# MCU.net
KiCad netlist of a schematic drawn in Altium Designer
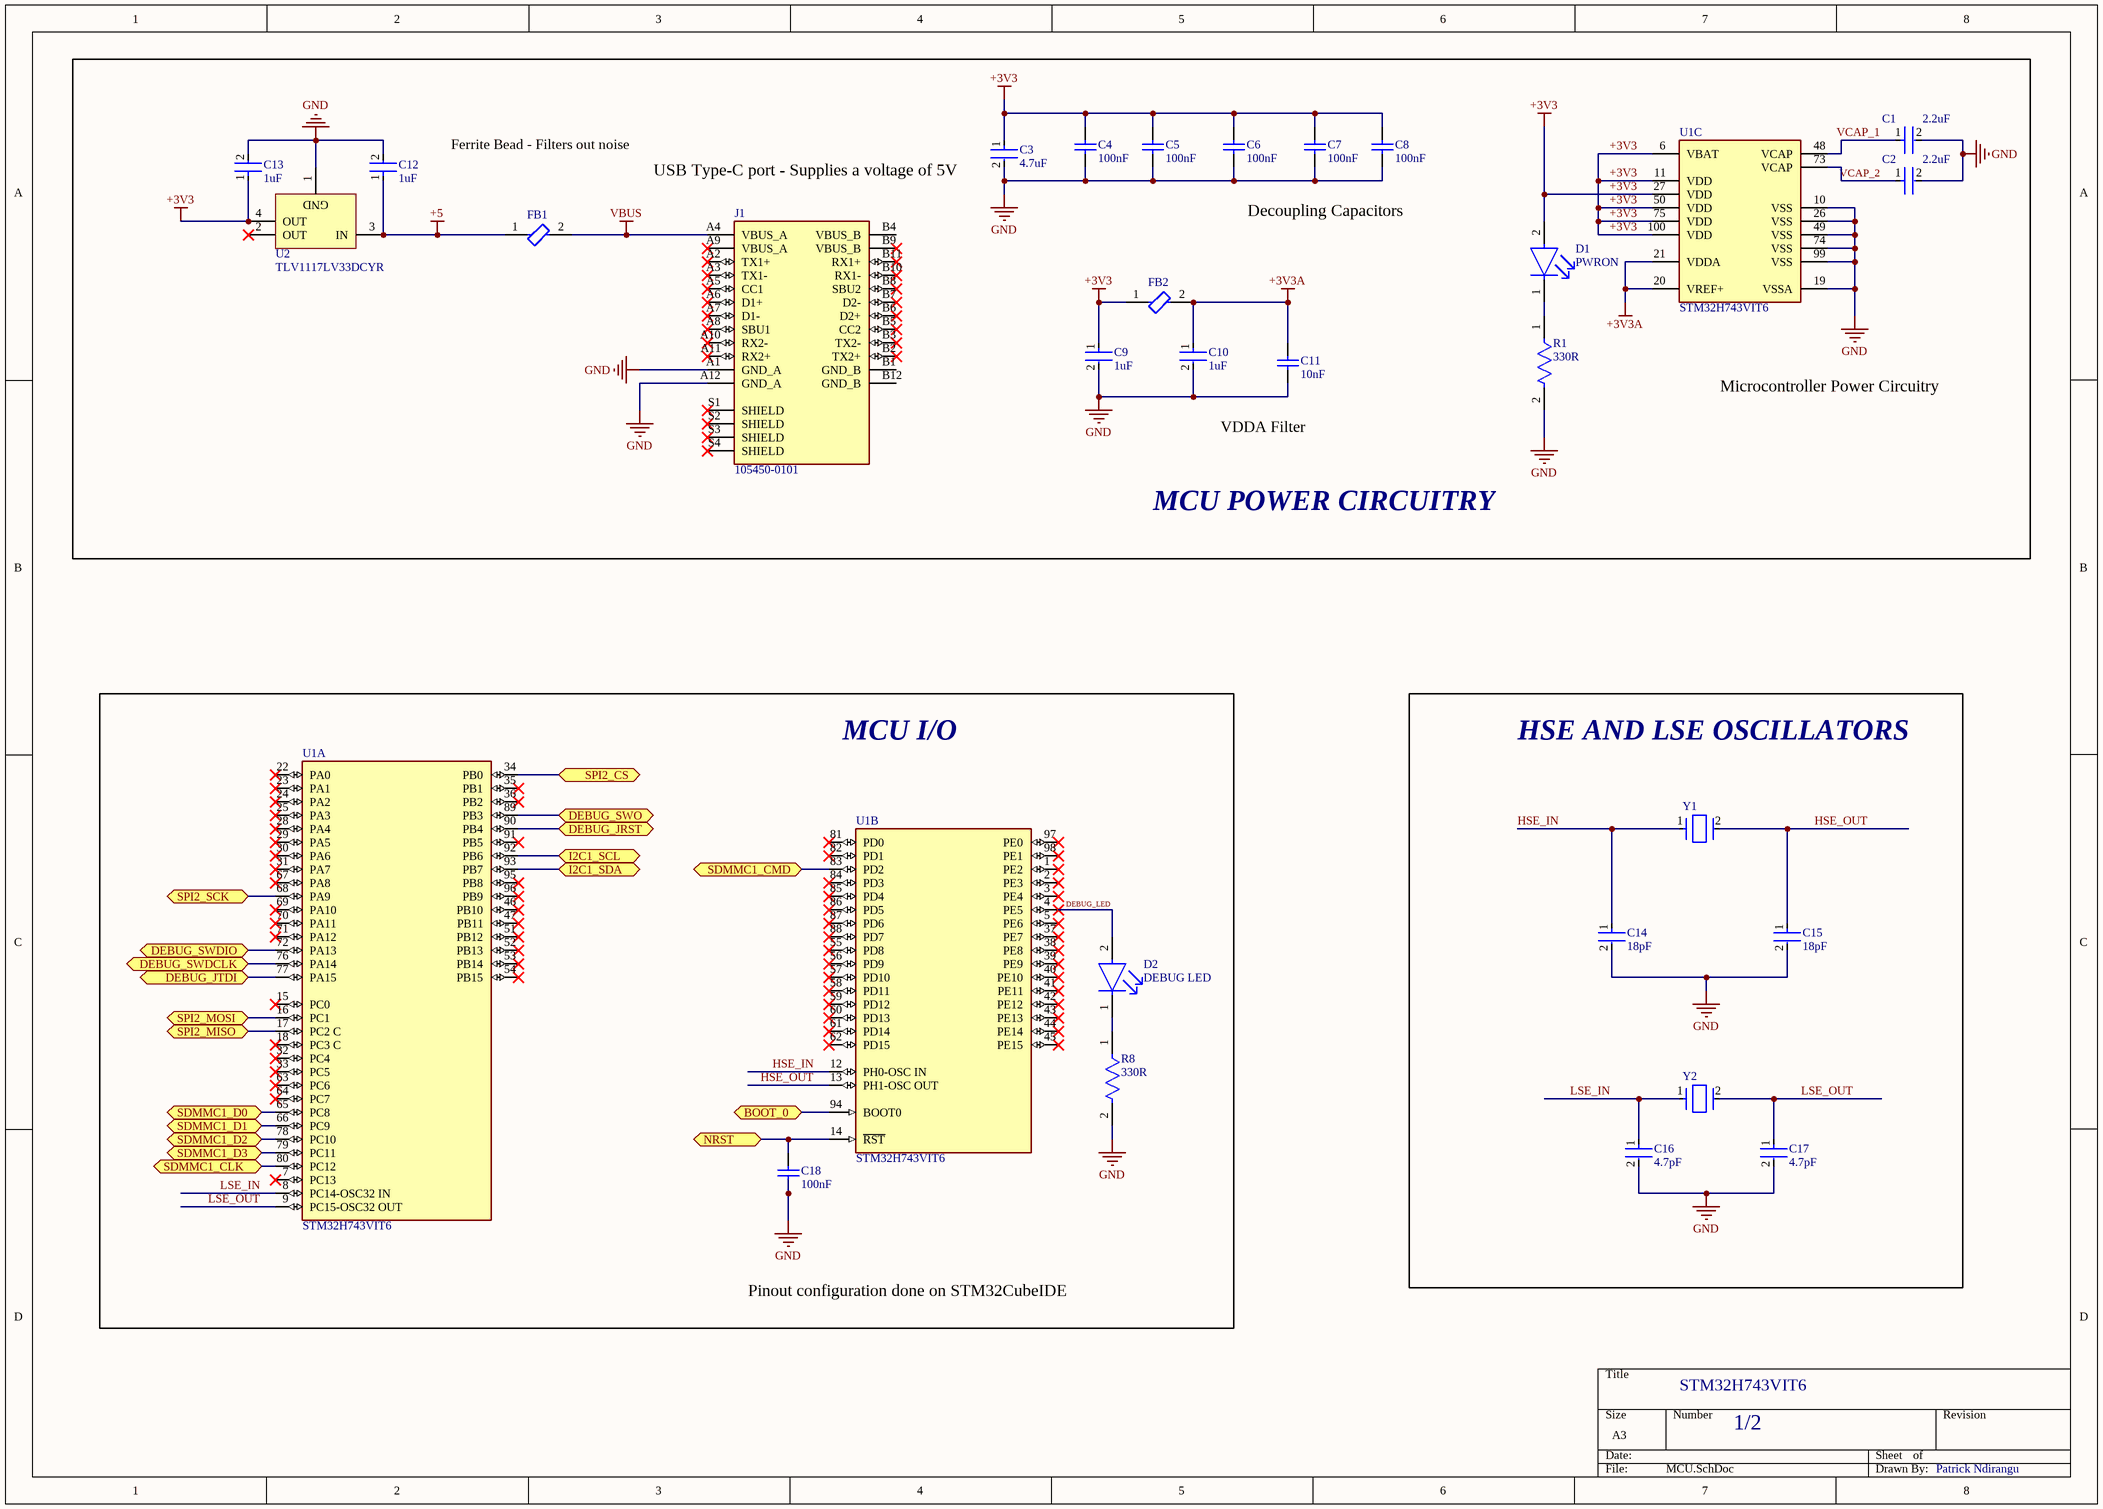
[diagram p0: MCU.SchDoc]

(export (version "E")
  (design (tool "Eeschema 10.0.6"))
  (components
    (comp (ref "C1")
      (value "2.2uF")
      (footprint "FP-0805-L_2_01_0_2-W_1_25-IPC_C")
      (description "General Purpose Ceramic Capacitor, 0805, 2.2uF, 10%, X5R, 15%, 25V")
      (fields (field (name "TOLERANCE") "10%"))
      (libsource (lib "Altium Content Vault") (part "b4654b650e69147ec39a6b967a45e02"))
    )
    (comp (ref "C2")
      (value "2.2uF")
      (footprint "FP-0805-L_2_01_0_2-W_1_25-IPC_C")
      (description "General Purpose Ceramic Capacitor, 0805, 2.2uF, 10%, X5R, 15%, 25V")
      (fields (field (name "TOLERANCE") "10%"))
      (libsource (lib "Altium Content Vault") (part "b4654b650e69147ec39a6b967a45e02"))
    )
    (comp (ref "C3")
      (value "4.7uF")
      (footprint "FP-CL21-IPC_A")
      (description "CL21 Series 0805 4.7uF 25V ±10% Tolerance X5R Multilayer Ceramic Chip Capacitor")
      (fields (field (name "TOLERANCE") "10%"))
      (libsource (lib "Altium Content Vault") (part "b4654b650e69147ec39a6b967a45e02"))
    )
    (comp (ref "C4")
      (value "100nF")
      (footprint "CAPC1050X55X23ML05T13")
      (description "Chip Capacitor, 100 nF, +/- 10%, 16 V, -55 to 125 degC, 0402 (1005 Metric), RoHS, Tape and Reel")
      (fields (field (name "MANUFACTURER") "Samsung Electro-Mechanics"))
      (libsource (lib "Altium Content Vault") (part "CAP-NP-2"))
    )
    (comp (ref "C5")
      (value "100nF")
      (footprint "CAPC1050X55X23ML05T13")
      (description "Chip Capacitor, 100 nF, +/- 10%, 16 V, -55 to 125 degC, 0402 (1005 Metric), RoHS, Tape and Reel")
      (fields (field (name "MANUFACTURER") "Samsung Electro-Mechanics"))
      (libsource (lib "Altium Content Vault") (part "CAP-NP-2"))
    )
    (comp (ref "C6")
      (value "100nF")
      (footprint "CAPC1050X55X23ML05T13")
      (description "Chip Capacitor, 100 nF, +/- 10%, 16 V, -55 to 125 degC, 0402 (1005 Metric), RoHS, Tape and Reel")
      (fields (field (name "MANUFACTURER") "Samsung Electro-Mechanics"))
      (libsource (lib "Altium Content Vault") (part "CAP-NP-2"))
    )
    (comp (ref "C7")
      (value "100nF")
      (footprint "CAPC1050X55X23ML05T13")
      (description "Chip Capacitor, 100 nF, +/- 10%, 16 V, -55 to 125 degC, 0402 (1005 Metric), RoHS, Tape and Reel")
      (fields (field (name "MANUFACTURER") "Samsung Electro-Mechanics"))
      (libsource (lib "Altium Content Vault") (part "CAP-NP-2"))
    )
    (comp (ref "C8")
      (value "100nF")
      (footprint "CAPC1050X55X23ML05T13")
      (description "Chip Capacitor, 100 nF, +/- 10%, 16 V, -55 to 125 degC, 0402 (1005 Metric), RoHS, Tape and Reel")
      (fields (field (name "MANUFACTURER") "Samsung Electro-Mechanics"))
      (libsource (lib "Altium Content Vault") (part "CAP-NP-2"))
    )
    (comp (ref "C9")
      (value "1uF")
      (footprint "FP-CL10-IPC_C")
      (description "Cap Ceramic 1uF 25V X5R ±10% Pad SMD 0603 +85°C T/R")
      (fields (field (name "VOLTAGE") "25V") (field (name "TOLERANCE") "10%"))
      (libsource (lib "Altium Content Vault") (part "b4654b650e69147ec39a6b967a45e02"))
    )
    (comp (ref "C10")
      (value "1uF")
      (footprint "FP-CL10-IPC_C")
      (description "Cap Ceramic 1uF 25V X5R ±10% Pad SMD 0603 +85°C T/R")
      (fields (field (name "VOLTAGE") "25V") (field (name "TOLERANCE") "10%"))
      (libsource (lib "Altium Content Vault") (part "b4654b650e69147ec39a6b967a45e02"))
    )
    (comp (ref "C11")
      (value "10nF")
      (footprint "CAPC1608X90X35ML10T15")
      (description "Chip Capacitor, 10 nF, +/- 10%, 50 V, -55 to 125 degC, 0603 (1608 Metric), RoHS, Tape and Reel")
      (fields (field (name "VOLTAGE") "50V") (field (name "TOLERANCE") "10%"))
      (libsource (lib "Altium Content Vault") (part "CAP-NP-2"))
    )
    (comp (ref "C12")
      (value "1uF")
      (footprint "FP-CL10-IPC_C")
      (description "Cap Ceramic 1uF 25V X5R ±10% Pad SMD 0603 +85°C T/R")
      (fields (field (name "VOLTAGE") "25V") (field (name "TOLERANCE") "10%"))
      (libsource (lib "Altium Content Vault") (part "b4654b650e69147ec39a6b967a45e02"))
    )
    (comp (ref "C13")
      (value "1uF")
      (footprint "FP-CL10-IPC_C")
      (description "Cap Ceramic 1uF 25V X5R ±10% Pad SMD 0603 +85°C T/R")
      (fields (field (name "VOLTAGE") "25V") (field (name "TOLERANCE") "10%"))
      (libsource (lib "Altium Content Vault") (part "b4654b650e69147ec39a6b967a45e02"))
    )
    (comp (ref "C14")
      (value "18pF")
      (footprint "FP-CL10-IPC_A")
      (description "Cap Ceramic 18pF 50V C0G ±5% Pad SMD 0603 +125°C T/R")
      (fields (field (name "TOLERANCE") "5%") (field (name "VOLTAGE") "50V"))
      (libsource (lib "Altium Content Vault") (part "b4654b650e69147ec39a6b967a45e02"))
    )
    (comp (ref "C15")
      (value "18pF")
      (footprint "FP-CL10-IPC_A")
      (description "Cap Ceramic 18pF 50V C0G ±5% Pad SMD 0603 +125°C T/R")
      (fields (field (name "TOLERANCE") "5%") (field (name "VOLTAGE") "50V"))
      (libsource (lib "Altium Content Vault") (part "b4654b650e69147ec39a6b967a45e02"))
    )
    (comp (ref "C16")
      (value "4.7pF")
      (footprint "FP-CL10-IPC_C")
      (description "Cap Ceramic 4.7pF 50V C0G ±0.25pF Pad SMD 0603 +125°C T/R")
      (fields (field (name "VOLTAGE") "50V"))
      (libsource (lib "Altium Content Vault") (part "b4654b650e69147ec39a6b967a45e02"))
    )
    (comp (ref "C17")
      (value "4.7pF")
      (footprint "FP-CL10-IPC_C")
      (description "Cap Ceramic 4.7pF 50V C0G ±0.25pF Pad SMD 0603 +125°C T/R")
      (fields (field (name "VOLTAGE") "50V"))
      (libsource (lib "Altium Content Vault") (part "b4654b650e69147ec39a6b967a45e02"))
    )
    (comp (ref "C18")
      (value "100nF")
      (footprint "CAPC1050X55X23ML05T13")
      (description "Chip Capacitor, 100 nF, +/- 10%, 16 V, -55 to 125 degC, 0402 (1005 Metric), RoHS, Tape and Reel")
      (fields (field (name "MANUFACTURER") "Samsung Electro-Mechanics"))
      (libsource (lib "Altium Content Vault") (part "CAP-NP-2"))
    )
    (comp (ref "D1")
      (value "PWRON")
      (footprint "FP-6_541-5092_01-4-MFG")
      (description "LED RED 0603 SMD")
      (fields
        (field (name "MANUFACTURER") "Vishay")
        (field (name "MANUFACTURER PART NUMBER") "VLMS1300-GS08")
      )
      (libsource (lib "Altium Content Vault") (part "8706943c75ba83719d021d2fdc84c58"))
    )
    (comp (ref "D2")
      (value "DEBUG LED")
      (footprint "FP-6_541-5094_01-4-MFG")
      (description "LED BLUE 0603 SMD")
      (fields
        (field (name "MANUFACTURER PART NUMBER") "VLMB1300-GS08")
        (field (name "MANUFACTURER") "Vishay Semiconductor Opto Division")
      )
      (libsource (lib "Altium Content Vault") (part "8706943c75ba83719d021d2fdc84c58"))
    )
    (comp (ref "FB1")
      (value "MMZ1005D121CTD25")
      (footprint "FP-MMZ1005-IPC_C")
      (description "Signal Line Ferrite Bead 120Ω @ 100MHz 350mA DCR 600mΩ AEC-Q200 SMD 0402")
      (libsource (lib "Altium Content Vault") (part "5f30dd21d616792df468990f7003faa"))
    )
    (comp (ref "FB2")
      (value "MMZ1005D121CTD25")
      (footprint "FP-MMZ1005-IPC_C")
      (description "Signal Line Ferrite Bead 120Ω @ 100MHz 350mA DCR 600mΩ AEC-Q200 SMD 0402")
      (libsource (lib "Altium Content Vault") (part "5f30dd21d616792df468990f7003faa"))
    )
    (comp (ref "J1")
      (value "105450-0101")
      (footprint "MOLEX_105450-0101")
      (fields
        (field (name "MF") "Molex")
        (field (name "DIGI-KEY_PART_NUMBER") "WM12856TR-ND")
        (field (name "MP") "1054500101")
      )
      (libsource (lib "105450-0101") (part "105450-0101"))
    )
    (comp (ref "R1")
      (value "330R")
      (footprint "FP-KTR03-MFG")
      (description "Res Thick Film 0603 330Ω 1% 0.1W ±100ppm/°C Automotive Paper T/R")
      (fields (field (name "TOLERANCE") "1%"))
      (libsource (lib "Altium Content Vault") (part "1029c3af85768c4190bb7ad29bc67b5"))
    )
    (comp (ref "R8")
      (value "330R")
      (footprint "FP-KTR03-MFG")
      (description "Res Thick Film 0603 330Ω 1% 0.1W ±100ppm/°C Automotive Paper T/R")
      (fields (field (name "TOLERANCE") "1%"))
      (libsource (lib "Altium Content Vault") (part "1029c3af85768c4190bb7ad29bc67b5"))
    )
    (comp (ref "U1")
      (value "STM32H743VIT6")
      (footprint "FP-LQFP100-1L-MFG")
      (description "IC MCU 32BIT 2MB FLASH 100LQFP")
      (fields
        (field (name "OCTOPART") "https://octopart.com/stm32h743vit6-stmicroelectronics-76372527")
        (field (name "MANUFACTURER") "STMicroelectronics")
      )
      (libsource (lib "Altium Content Vault") (part "01082ce2885d1d16a22823c45526fe6"))
    )
    (comp (ref "U2")
      (value "TLV1117LV33DCYR")
      (footprint "DCY0004A_N")
      (fields (field (name "MANUFACTURER") "Texas Instruments"))
      (libsource (lib "Altium Content Vault") (part "TI-TLV1117LV33DCY4"))
    )
    (comp (ref "Y1")
      (value "ABM2-25.000MHZ-D4Y-T")
      (footprint "FP-ABM2-MFG")
      (description "Crystal 25MHz ±30ppm 18pF SMD-2 8mm x 4.5mm")
      (fields (field (name "TOLERANCE") "30ppm"))
      (libsource (lib "Altium Content Vault") (part "c23a69dc6c9e2f18f2079038eb95dd1"))
    )
    (comp (ref "Y2")
      (value "ABS06-107-32.768KHZ-T")
      (footprint "FP-ABS06-MFG")
      (description "Crystal 32.768kHz ±20ppm (Tol) 4pF FUND 60kΩ 2-Pin Mini-CSMD T/R")
      (fields (field (name "TOLERANCE") "20ppm"))
      (libsource (lib "Altium Content Vault") (part "c23a69dc6c9e2f18f2079038eb95dd1"))
    )
  )
  (nets
    (net (code "1") (name "+3V3") (class "Default")
      (node (ref "C13") (pin "1") (pinfunction "1_1") (pintype "passive"))
      (node (ref "C3") (pin "1") (pinfunction "1_1") (pintype "passive"))
      (node (ref "C4") (pin "2") (pinfunction "2_2") (pintype "passive"))
      (node (ref "C5") (pin "2") (pinfunction "2_2") (pintype "passive"))
      (node (ref "C6") (pin "2") (pinfunction "2_2") (pintype "passive"))
      (node (ref "C7") (pin "2") (pinfunction "2_2") (pintype "passive"))
      (node (ref "C8") (pin "2") (pinfunction "2_2") (pintype "passive"))
      (node (ref "C9") (pin "1") (pinfunction "1_1") (pintype "passive"))
      (node (ref "D1") (pin "2") (pinfunction "A_2") (pintype "passive"))
      (node (ref "FB2") (pin "1") (pinfunction "1_1") (pintype "passive"))
      (node (ref "U1") (pin "100") (pinfunction "VDD_100") (pintype "power_in"))
      (node (ref "U1") (pin "11") (pinfunction "VDD_11") (pintype "power_in"))
      (node (ref "U1") (pin "27") (pinfunction "VDD_27") (pintype "power_in"))
      (node (ref "U1") (pin "50") (pinfunction "VDD_50") (pintype "power_in"))
      (node (ref "U1") (pin "6") (pinfunction "VBAT_6") (pintype "power_in"))
      (node (ref "U1") (pin "75") (pinfunction "VDD_75") (pintype "power_in"))
      (node (ref "U2") (pin "4") (pinfunction "OUT_4") (pintype "power_in"))
    )
    (net (code "2") (name "+3V3A") (class "Default")
      (node (ref "C10") (pin "1") (pinfunction "1_1") (pintype "passive"))
      (node (ref "C11") (pin "2") (pinfunction "2_2") (pintype "passive"))
      (node (ref "FB2") (pin "2") (pinfunction "2_2") (pintype "passive"))
      (node (ref "U1") (pin "20") (pinfunction "VREF+_20") (pintype "power_in"))
      (node (ref "U1") (pin "21") (pinfunction "VDDA_21") (pintype "power_in"))
    )
    (net (code "3") (name "+5") (class "Default")
      (node (ref "C12") (pin "1") (pinfunction "1_1") (pintype "passive"))
      (node (ref "FB1") (pin "1") (pinfunction "1_1") (pintype "passive"))
      (node (ref "U2") (pin "3") (pinfunction "IN_3") (pintype "power_in"))
    )
    (net (code "4") (name "/BOOT_0") (class "Default")
      (node (ref "U1") (pin "94") (pinfunction "BOOT0_94") (pintype "input"))
    )
    (net (code "5") (name "/DEBUG_JRST") (class "Default")
      (node (ref "U1") (pin "90") (pinfunction "PB4_90") (pintype "bidirectional"))
    )
    (net (code "6") (name "/DEBUG_JTDI") (class "Default")
      (node (ref "U1") (pin "77") (pinfunction "PA15_77") (pintype "bidirectional"))
    )
    (net (code "7") (name "/DEBUG_LED") (class "Default")
      (node (ref "D2") (pin "2") (pinfunction "A_2") (pintype "passive"))
      (node (ref "U1") (pin "4") (pinfunction "PE5_4") (pintype "bidirectional"))
    )
    (net (code "8") (name "/DEBUG_SWDCLK") (class "Default")
      (node (ref "U1") (pin "76") (pinfunction "PA14_76") (pintype "bidirectional"))
    )
    (net (code "9") (name "/DEBUG_SWDIO") (class "Default")
      (node (ref "U1") (pin "72") (pinfunction "PA13_72") (pintype "bidirectional"))
    )
    (net (code "10") (name "/DEBUG_SWO") (class "Default")
      (node (ref "U1") (pin "89") (pinfunction "PB3_89") (pintype "bidirectional"))
    )
    (net (code "11") (name "/HSE_IN") (class "Default")
      (node (ref "C14") (pin "1") (pinfunction "1_1") (pintype "passive"))
      (node (ref "U1") (pin "12") (pinfunction "PH0-OSC_IN_12") (pintype "bidirectional"))
      (node (ref "Y1") (pin "1") (pinfunction "1_1") (pintype "passive"))
    )
    (net (code "12") (name "/HSE_OUT") (class "Default")
      (node (ref "C15") (pin "1") (pinfunction "1_1") (pintype "passive"))
      (node (ref "U1") (pin "13") (pinfunction "PH1-OSC_OUT_13") (pintype "bidirectional"))
      (node (ref "Y1") (pin "2") (pinfunction "2_2") (pintype "passive"))
    )
    (net (code "13") (name "/I2C1_SCL") (class "Default")
      (node (ref "U1") (pin "92") (pinfunction "PB6_92") (pintype "bidirectional"))
    )
    (net (code "14") (name "/I2C1_SDA") (class "Default")
      (node (ref "U1") (pin "93") (pinfunction "PB7_93") (pintype "bidirectional"))
    )
    (net (code "15") (name "/LSE_IN") (class "Default")
      (node (ref "C16") (pin "1") (pinfunction "1_1") (pintype "passive"))
      (node (ref "U1") (pin "8") (pinfunction "PC14-OSC32_IN_8") (pintype "bidirectional"))
      (node (ref "Y2") (pin "1") (pinfunction "1_1") (pintype "passive"))
    )
    (net (code "16") (name "/LSE_OUT") (class "Default")
      (node (ref "C17") (pin "1") (pinfunction "1_1") (pintype "passive"))
      (node (ref "U1") (pin "9") (pinfunction "PC15-OSC32_OUT_9") (pintype "bidirectional"))
      (node (ref "Y2") (pin "2") (pinfunction "2_2") (pintype "passive"))
    )
    (net (code "17") (name "/NRST") (class "Default")
      (node (ref "C18") (pin "2") (pinfunction "2_2") (pintype "passive"))
      (node (ref "U1") (pin "14") (pinfunction "~{RST}_14") (pintype "input"))
    )
    (net (code "18") (name "/SDMMC1_CLK") (class "Default")
      (node (ref "U1") (pin "80") (pinfunction "PC12_80") (pintype "bidirectional"))
    )
    (net (code "19") (name "/SDMMC1_CMD") (class "Default")
      (node (ref "U1") (pin "83") (pinfunction "PD2_83") (pintype "bidirectional"))
    )
    (net (code "20") (name "/SDMMC1_D0") (class "Default")
      (node (ref "U1") (pin "65") (pinfunction "PC8_65") (pintype "bidirectional"))
    )
    (net (code "21") (name "/SDMMC1_D1") (class "Default")
      (node (ref "U1") (pin "66") (pinfunction "PC9_66") (pintype "bidirectional"))
    )
    (net (code "22") (name "/SDMMC1_D2") (class "Default")
      (node (ref "U1") (pin "78") (pinfunction "PC10_78") (pintype "bidirectional"))
    )
    (net (code "23") (name "/SDMMC1_D3") (class "Default")
      (node (ref "U1") (pin "79") (pinfunction "PC11_79") (pintype "bidirectional"))
    )
    (net (code "24") (name "/SPI2_CS") (class "Default")
      (node (ref "U1") (pin "34") (pinfunction "PB0_34") (pintype "bidirectional"))
    )
    (net (code "25") (name "/SPI2_MISO") (class "Default")
      (node (ref "U1") (pin "17") (pinfunction "PC2_C_17") (pintype "bidirectional"))
    )
    (net (code "26") (name "/SPI2_MOSI") (class "Default")
      (node (ref "U1") (pin "16") (pinfunction "PC1_16") (pintype "bidirectional"))
    )
    (net (code "27") (name "/SPI2_SCK") (class "Default")
      (node (ref "U1") (pin "68") (pinfunction "PA9_68") (pintype "bidirectional"))
    )
    (net (code "28") (name "/VCAP_1") (class "Default")
      (node (ref "C1") (pin "1") (pinfunction "1_1") (pintype "passive"))
      (node (ref "U1") (pin "48") (pinfunction "VCAP_48") (pintype "passive"))
    )
    (net (code "29") (name "/VCAP_2") (class "Default")
      (node (ref "C2") (pin "1") (pinfunction "1_1") (pintype "passive"))
      (node (ref "U1") (pin "73") (pinfunction "VCAP_73") (pintype "passive"))
    )
    (net (code "30") (name "GND") (class "Default")
      (node (ref "C1") (pin "2") (pinfunction "2_2") (pintype "passive"))
      (node (ref "C10") (pin "2") (pinfunction "2_2") (pintype "passive"))
      (node (ref "C11") (pin "1") (pinfunction "1_1") (pintype "passive"))
      (node (ref "C12") (pin "2") (pinfunction "2_2") (pintype "passive"))
      (node (ref "C13") (pin "2") (pinfunction "2_2") (pintype "passive"))
      (node (ref "C14") (pin "2") (pinfunction "2_2") (pintype "passive"))
      (node (ref "C15") (pin "2") (pinfunction "2_2") (pintype "passive"))
      (node (ref "C16") (pin "2") (pinfunction "2_2") (pintype "passive"))
      (node (ref "C17") (pin "2") (pinfunction "2_2") (pintype "passive"))
      (node (ref "C18") (pin "1") (pinfunction "1_1") (pintype "passive"))
      (node (ref "C2") (pin "2") (pinfunction "2_2") (pintype "passive"))
      (node (ref "C3") (pin "2") (pinfunction "2_2") (pintype "passive"))
      (node (ref "C4") (pin "1") (pinfunction "1_1") (pintype "passive"))
      (node (ref "C5") (pin "1") (pinfunction "1_1") (pintype "passive"))
      (node (ref "C6") (pin "1") (pinfunction "1_1") (pintype "passive"))
      (node (ref "C7") (pin "1") (pinfunction "1_1") (pintype "passive"))
      (node (ref "C8") (pin "1") (pinfunction "1_1") (pintype "passive"))
      (node (ref "C9") (pin "2") (pinfunction "2_2") (pintype "passive"))
      (node (ref "J1") (pin "A1") (pinfunction "GND_A_A1") (pintype "power_in"))
      (node (ref "J1") (pin "A12") (pinfunction "GND_A_A12") (pintype "power_in"))
      (node (ref "R1") (pin "2") (pinfunction "2_2") (pintype "passive"))
      (node (ref "R8") (pin "2") (pinfunction "2_2") (pintype "passive"))
      (node (ref "U1") (pin "10") (pinfunction "VSS_10") (pintype "power_in"))
      (node (ref "U1") (pin "19") (pinfunction "VSSA_19") (pintype "power_in"))
      (node (ref "U1") (pin "26") (pinfunction "VSS_26") (pintype "power_in"))
      (node (ref "U1") (pin "49") (pinfunction "VSS_49") (pintype "power_in"))
      (node (ref "U1") (pin "74") (pinfunction "VSS_74") (pintype "power_in"))
      (node (ref "U1") (pin "99") (pinfunction "VSS_99") (pintype "power_in"))
      (node (ref "U2") (pin "1") (pinfunction "GND_1") (pintype "power_in"))
    )
    (net (code "31") (name "Net-(D1-C)") (class "Default")
      (node (ref "D1") (pin "1") (pinfunction "C_1") (pintype "passive"))
      (node (ref "R1") (pin "1") (pinfunction "1_1") (pintype "passive"))
    )
    (net (code "32") (name "Net-(D2-C)") (class "Default")
      (node (ref "D2") (pin "1") (pinfunction "C_1") (pintype "passive"))
      (node (ref "R8") (pin "1") (pinfunction "1_1") (pintype "passive"))
    )
    (net (code "33") (name "VBUS") (class "Default")
      (node (ref "FB1") (pin "2") (pinfunction "2_2") (pintype "passive"))
      (node (ref "J1") (pin "A4") (pinfunction "VBUS_A_A4") (pintype "power_in"))
    )
    (net (code "34") (name "unconnected-(J1-CC1-PadA5)") (class "Default")
      (node (ref "J1") (pin "A5") (pinfunction "CC1_A5") (pintype "bidirectional+no_connect"))
    )
    (net (code "35") (name "unconnected-(J1-CC2-PadB5)") (class "Default")
      (node (ref "J1") (pin "B5") (pinfunction "CC2_B5") (pintype "bidirectional+no_connect"))
    )
    (net (code "36") (name "unconnected-(J1-D1+-PadA6)") (class "Default")
      (node (ref "J1") (pin "A6") (pinfunction "D1+_A6") (pintype "bidirectional+no_connect"))
    )
    (net (code "37") (name "unconnected-(J1-D1--PadA7)") (class "Default")
      (node (ref "J1") (pin "A7") (pinfunction "D1-_A7") (pintype "bidirectional+no_connect"))
    )
    (net (code "38") (name "unconnected-(J1-D2+-PadB6)") (class "Default")
      (node (ref "J1") (pin "B6") (pinfunction "D2+_B6") (pintype "bidirectional+no_connect"))
    )
    (net (code "39") (name "unconnected-(J1-D2--PadB7)") (class "Default")
      (node (ref "J1") (pin "B7") (pinfunction "D2-_B7") (pintype "bidirectional+no_connect"))
    )
    (net (code "40") (name "unconnected-(J1-GND_B-PadB1)") (class "Default")
      (node (ref "J1") (pin "B1") (pinfunction "GND_B_B1") (pintype "power_in"))
    )
    (net (code "41") (name "unconnected-(J1-GND_B-PadB12)") (class "Default")
      (node (ref "J1") (pin "B12") (pinfunction "GND_B_B12") (pintype "power_in"))
    )
    (net (code "42") (name "unconnected-(J1-RX1+-PadB11)") (class "Default")
      (node (ref "J1") (pin "B11") (pinfunction "RX1+_B11") (pintype "bidirectional+no_connect"))
    )
    (net (code "43") (name "unconnected-(J1-RX1--PadB10)") (class "Default")
      (node (ref "J1") (pin "B10") (pinfunction "RX1-_B10") (pintype "bidirectional+no_connect"))
    )
    (net (code "44") (name "unconnected-(J1-RX2+-PadA11)") (class "Default")
      (node (ref "J1") (pin "A11") (pinfunction "RX2+_A11") (pintype "bidirectional+no_connect"))
    )
    (net (code "45") (name "unconnected-(J1-RX2--PadA10)") (class "Default")
      (node (ref "J1") (pin "A10") (pinfunction "RX2-_A10") (pintype "bidirectional+no_connect"))
    )
    (net (code "46") (name "unconnected-(J1-SBU1-PadA8)") (class "Default")
      (node (ref "J1") (pin "A8") (pinfunction "SBU1_A8") (pintype "bidirectional+no_connect"))
    )
    (net (code "47") (name "unconnected-(J1-SBU2-PadB8)") (class "Default")
      (node (ref "J1") (pin "B8") (pinfunction "SBU2_B8") (pintype "bidirectional+no_connect"))
    )
    (net (code "48") (name "unconnected-(J1-SHIELD-PadS1)") (class "Default")
      (node (ref "J1") (pin "S1") (pinfunction "SHIELD_S1") (pintype "passive+no_connect"))
    )
    (net (code "49") (name "unconnected-(J1-SHIELD-PadS2)") (class "Default")
      (node (ref "J1") (pin "S2") (pinfunction "SHIELD_S2") (pintype "passive+no_connect"))
    )
    (net (code "50") (name "unconnected-(J1-SHIELD-PadS3)") (class "Default")
      (node (ref "J1") (pin "S3") (pinfunction "SHIELD_S3") (pintype "passive+no_connect"))
    )
    (net (code "51") (name "unconnected-(J1-SHIELD-PadS4)") (class "Default")
      (node (ref "J1") (pin "S4") (pinfunction "SHIELD_S4") (pintype "passive+no_connect"))
    )
    (net (code "52") (name "unconnected-(J1-TX1+-PadA2)") (class "Default")
      (node (ref "J1") (pin "A2") (pinfunction "TX1+_A2") (pintype "bidirectional+no_connect"))
    )
    (net (code "53") (name "unconnected-(J1-TX1--PadA3)") (class "Default")
      (node (ref "J1") (pin "A3") (pinfunction "TX1-_A3") (pintype "bidirectional+no_connect"))
    )
    (net (code "54") (name "unconnected-(J1-TX2+-PadB2)") (class "Default")
      (node (ref "J1") (pin "B2") (pinfunction "TX2+_B2") (pintype "bidirectional+no_connect"))
    )
    (net (code "55") (name "unconnected-(J1-TX2--PadB3)") (class "Default")
      (node (ref "J1") (pin "B3") (pinfunction "TX2-_B3") (pintype "bidirectional+no_connect"))
    )
    (net (code "56") (name "unconnected-(J1-VBUS_A-PadA9)") (class "Default")
      (node (ref "J1") (pin "A9") (pinfunction "VBUS_A_A9") (pintype "power_in+no_connect"))
    )
    (net (code "57") (name "unconnected-(J1-VBUS_B-PadB4)") (class "Default")
      (node (ref "J1") (pin "B4") (pinfunction "VBUS_B_B4") (pintype "power_in"))
    )
    (net (code "58") (name "unconnected-(J1-VBUS_B-PadB9)") (class "Default")
      (node (ref "J1") (pin "B9") (pinfunction "VBUS_B_B9") (pintype "power_in+no_connect"))
    )
    (net (code "59") (name "unconnected-(U1A-PA0-Pad22)") (class "Default")
      (node (ref "U1") (pin "22") (pinfunction "PA0_22") (pintype "bidirectional+no_connect"))
    )
    (net (code "60") (name "unconnected-(U1A-PA1-Pad23)") (class "Default")
      (node (ref "U1") (pin "23") (pinfunction "PA1_23") (pintype "bidirectional+no_connect"))
    )
    (net (code "61") (name "unconnected-(U1A-PA2-Pad24)") (class "Default")
      (node (ref "U1") (pin "24") (pinfunction "PA2_24") (pintype "bidirectional+no_connect"))
    )
    (net (code "62") (name "unconnected-(U1A-PA3-Pad25)") (class "Default")
      (node (ref "U1") (pin "25") (pinfunction "PA3_25") (pintype "bidirectional+no_connect"))
    )
    (net (code "63") (name "unconnected-(U1A-PA4-Pad28)") (class "Default")
      (node (ref "U1") (pin "28") (pinfunction "PA4_28") (pintype "bidirectional+no_connect"))
    )
    (net (code "64") (name "unconnected-(U1A-PA5-Pad29)") (class "Default")
      (node (ref "U1") (pin "29") (pinfunction "PA5_29") (pintype "bidirectional+no_connect"))
    )
    (net (code "65") (name "unconnected-(U1A-PA6-Pad30)") (class "Default")
      (node (ref "U1") (pin "30") (pinfunction "PA6_30") (pintype "bidirectional+no_connect"))
    )
    (net (code "66") (name "unconnected-(U1A-PA7-Pad31)") (class "Default")
      (node (ref "U1") (pin "31") (pinfunction "PA7_31") (pintype "bidirectional+no_connect"))
    )
    (net (code "67") (name "unconnected-(U1A-PA8-Pad67)") (class "Default")
      (node (ref "U1") (pin "67") (pinfunction "PA8_67") (pintype "bidirectional+no_connect"))
    )
    (net (code "68") (name "unconnected-(U1A-PA10-Pad69)") (class "Default")
      (node (ref "U1") (pin "69") (pinfunction "PA10_69") (pintype "bidirectional+no_connect"))
    )
    (net (code "69") (name "unconnected-(U1A-PA11-Pad70)") (class "Default")
      (node (ref "U1") (pin "70") (pinfunction "PA11_70") (pintype "bidirectional+no_connect"))
    )
    (net (code "70") (name "unconnected-(U1A-PA12-Pad71)") (class "Default")
      (node (ref "U1") (pin "71") (pinfunction "PA12_71") (pintype "bidirectional+no_connect"))
    )
    (net (code "71") (name "unconnected-(U1A-PB1-Pad35)") (class "Default")
      (node (ref "U1") (pin "35") (pinfunction "PB1_35") (pintype "bidirectional+no_connect"))
    )
    (net (code "72") (name "unconnected-(U1A-PB2-Pad36)") (class "Default")
      (node (ref "U1") (pin "36") (pinfunction "PB2_36") (pintype "bidirectional+no_connect"))
    )
    (net (code "73") (name "unconnected-(U1A-PB5-Pad91)") (class "Default")
      (node (ref "U1") (pin "91") (pinfunction "PB5_91") (pintype "bidirectional+no_connect"))
    )
    (net (code "74") (name "unconnected-(U1A-PB8-Pad95)") (class "Default")
      (node (ref "U1") (pin "95") (pinfunction "PB8_95") (pintype "bidirectional+no_connect"))
    )
    (net (code "75") (name "unconnected-(U1A-PB9-Pad96)") (class "Default")
      (node (ref "U1") (pin "96") (pinfunction "PB9_96") (pintype "bidirectional+no_connect"))
    )
    (net (code "76") (name "unconnected-(U1A-PB10-Pad46)") (class "Default")
      (node (ref "U1") (pin "46") (pinfunction "PB10_46") (pintype "bidirectional+no_connect"))
    )
    (net (code "77") (name "unconnected-(U1A-PB11-Pad47)") (class "Default")
      (node (ref "U1") (pin "47") (pinfunction "PB11_47") (pintype "bidirectional+no_connect"))
    )
    (net (code "78") (name "unconnected-(U1A-PB12-Pad51)") (class "Default")
      (node (ref "U1") (pin "51") (pinfunction "PB12_51") (pintype "bidirectional+no_connect"))
    )
    (net (code "79") (name "unconnected-(U1A-PB13-Pad52)") (class "Default")
      (node (ref "U1") (pin "52") (pinfunction "PB13_52") (pintype "bidirectional+no_connect"))
    )
    (net (code "80") (name "unconnected-(U1A-PB14-Pad53)") (class "Default")
      (node (ref "U1") (pin "53") (pinfunction "PB14_53") (pintype "bidirectional+no_connect"))
    )
    (net (code "81") (name "unconnected-(U1A-PB15-Pad54)") (class "Default")
      (node (ref "U1") (pin "54") (pinfunction "PB15_54") (pintype "bidirectional+no_connect"))
    )
    (net (code "82") (name "unconnected-(U1A-PC0-Pad15)") (class "Default")
      (node (ref "U1") (pin "15") (pinfunction "PC0_15") (pintype "bidirectional+no_connect"))
    )
    (net (code "83") (name "unconnected-(U1A-PC3_C-Pad18)") (class "Default")
      (node (ref "U1") (pin "18") (pinfunction "PC3_C_18") (pintype "bidirectional+no_connect"))
    )
    (net (code "84") (name "unconnected-(U1A-PC4-Pad32)") (class "Default")
      (node (ref "U1") (pin "32") (pinfunction "PC4_32") (pintype "bidirectional+no_connect"))
    )
    (net (code "85") (name "unconnected-(U1A-PC5-Pad33)") (class "Default")
      (node (ref "U1") (pin "33") (pinfunction "PC5_33") (pintype "bidirectional+no_connect"))
    )
    (net (code "86") (name "unconnected-(U1A-PC6-Pad63)") (class "Default")
      (node (ref "U1") (pin "63") (pinfunction "PC6_63") (pintype "bidirectional+no_connect"))
    )
    (net (code "87") (name "unconnected-(U1A-PC7-Pad64)") (class "Default")
      (node (ref "U1") (pin "64") (pinfunction "PC7_64") (pintype "bidirectional+no_connect"))
    )
    (net (code "88") (name "unconnected-(U1A-PC13-Pad7)") (class "Default")
      (node (ref "U1") (pin "7") (pinfunction "PC13_7") (pintype "bidirectional+no_connect"))
    )
    (net (code "89") (name "unconnected-(U1B-PD0-Pad81)") (class "Default")
      (node (ref "U1") (pin "81") (pinfunction "PD0_81") (pintype "bidirectional+no_connect"))
    )
    (net (code "90") (name "unconnected-(U1B-PD1-Pad82)") (class "Default")
      (node (ref "U1") (pin "82") (pinfunction "PD1_82") (pintype "bidirectional+no_connect"))
    )
    (net (code "91") (name "unconnected-(U1B-PD3-Pad84)") (class "Default")
      (node (ref "U1") (pin "84") (pinfunction "PD3_84") (pintype "bidirectional+no_connect"))
    )
    (net (code "92") (name "unconnected-(U1B-PD4-Pad85)") (class "Default")
      (node (ref "U1") (pin "85") (pinfunction "PD4_85") (pintype "bidirectional+no_connect"))
    )
    (net (code "93") (name "unconnected-(U1B-PD5-Pad86)") (class "Default")
      (node (ref "U1") (pin "86") (pinfunction "PD5_86") (pintype "bidirectional+no_connect"))
    )
    (net (code "94") (name "unconnected-(U1B-PD6-Pad87)") (class "Default")
      (node (ref "U1") (pin "87") (pinfunction "PD6_87") (pintype "bidirectional+no_connect"))
    )
    (net (code "95") (name "unconnected-(U1B-PD7-Pad88)") (class "Default")
      (node (ref "U1") (pin "88") (pinfunction "PD7_88") (pintype "bidirectional+no_connect"))
    )
    (net (code "96") (name "unconnected-(U1B-PD8-Pad55)") (class "Default")
      (node (ref "U1") (pin "55") (pinfunction "PD8_55") (pintype "bidirectional+no_connect"))
    )
    (net (code "97") (name "unconnected-(U1B-PD9-Pad56)") (class "Default")
      (node (ref "U1") (pin "56") (pinfunction "PD9_56") (pintype "bidirectional+no_connect"))
    )
    (net (code "98") (name "unconnected-(U1B-PD10-Pad57)") (class "Default")
      (node (ref "U1") (pin "57") (pinfunction "PD10_57") (pintype "bidirectional+no_connect"))
    )
    (net (code "99") (name "unconnected-(U1B-PD11-Pad58)") (class "Default")
      (node (ref "U1") (pin "58") (pinfunction "PD11_58") (pintype "bidirectional+no_connect"))
    )
    (net (code "100") (name "unconnected-(U1B-PD12-Pad59)") (class "Default")
      (node (ref "U1") (pin "59") (pinfunction "PD12_59") (pintype "bidirectional+no_connect"))
    )
    (net (code "101") (name "unconnected-(U1B-PD13-Pad60)") (class "Default")
      (node (ref "U1") (pin "60") (pinfunction "PD13_60") (pintype "bidirectional+no_connect"))
    )
    (net (code "102") (name "unconnected-(U1B-PD14-Pad61)") (class "Default")
      (node (ref "U1") (pin "61") (pinfunction "PD14_61") (pintype "bidirectional+no_connect"))
    )
    (net (code "103") (name "unconnected-(U1B-PD15-Pad62)") (class "Default")
      (node (ref "U1") (pin "62") (pinfunction "PD15_62") (pintype "bidirectional+no_connect"))
    )
    (net (code "104") (name "unconnected-(U1B-PE0-Pad97)") (class "Default")
      (node (ref "U1") (pin "97") (pinfunction "PE0_97") (pintype "bidirectional+no_connect"))
    )
    (net (code "105") (name "unconnected-(U1B-PE1-Pad98)") (class "Default")
      (node (ref "U1") (pin "98") (pinfunction "PE1_98") (pintype "bidirectional+no_connect"))
    )
    (net (code "106") (name "unconnected-(U1B-PE2-Pad1)") (class "Default")
      (node (ref "U1") (pin "1") (pinfunction "PE2_1") (pintype "bidirectional+no_connect"))
    )
    (net (code "107") (name "unconnected-(U1B-PE3-Pad2)") (class "Default")
      (node (ref "U1") (pin "2") (pinfunction "PE3_2") (pintype "bidirectional+no_connect"))
    )
    (net (code "108") (name "unconnected-(U1B-PE4-Pad3)") (class "Default")
      (node (ref "U1") (pin "3") (pinfunction "PE4_3") (pintype "bidirectional+no_connect"))
    )
    (net (code "109") (name "unconnected-(U1B-PE6-Pad5)") (class "Default")
      (node (ref "U1") (pin "5") (pinfunction "PE6_5") (pintype "bidirectional+no_connect"))
    )
    (net (code "110") (name "unconnected-(U1B-PE7-Pad37)") (class "Default")
      (node (ref "U1") (pin "37") (pinfunction "PE7_37") (pintype "bidirectional+no_connect"))
    )
    (net (code "111") (name "unconnected-(U1B-PE8-Pad38)") (class "Default")
      (node (ref "U1") (pin "38") (pinfunction "PE8_38") (pintype "bidirectional+no_connect"))
    )
    (net (code "112") (name "unconnected-(U1B-PE9-Pad39)") (class "Default")
      (node (ref "U1") (pin "39") (pinfunction "PE9_39") (pintype "bidirectional+no_connect"))
    )
    (net (code "113") (name "unconnected-(U1B-PE10-Pad40)") (class "Default")
      (node (ref "U1") (pin "40") (pinfunction "PE10_40") (pintype "bidirectional+no_connect"))
    )
    (net (code "114") (name "unconnected-(U1B-PE11-Pad41)") (class "Default")
      (node (ref "U1") (pin "41") (pinfunction "PE11_41") (pintype "bidirectional+no_connect"))
    )
    (net (code "115") (name "unconnected-(U1B-PE12-Pad42)") (class "Default")
      (node (ref "U1") (pin "42") (pinfunction "PE12_42") (pintype "bidirectional+no_connect"))
    )
    (net (code "116") (name "unconnected-(U1B-PE13-Pad43)") (class "Default")
      (node (ref "U1") (pin "43") (pinfunction "PE13_43") (pintype "bidirectional+no_connect"))
    )
    (net (code "117") (name "unconnected-(U1B-PE14-Pad44)") (class "Default")
      (node (ref "U1") (pin "44") (pinfunction "PE14_44") (pintype "bidirectional+no_connect"))
    )
    (net (code "118") (name "unconnected-(U1B-PE15-Pad45)") (class "Default")
      (node (ref "U1") (pin "45") (pinfunction "PE15_45") (pintype "bidirectional+no_connect"))
    )
    (net (code "119") (name "unconnected-(U2-OUT-Pad2)") (class "Default")
      (node (ref "U2") (pin "2") (pinfunction "OUT_2") (pintype "power_in+no_connect"))
    )
  )
)
